# SCH_NodeMCU_PCB.net
KiCad netlist of a schematic drawn in EasyEDA
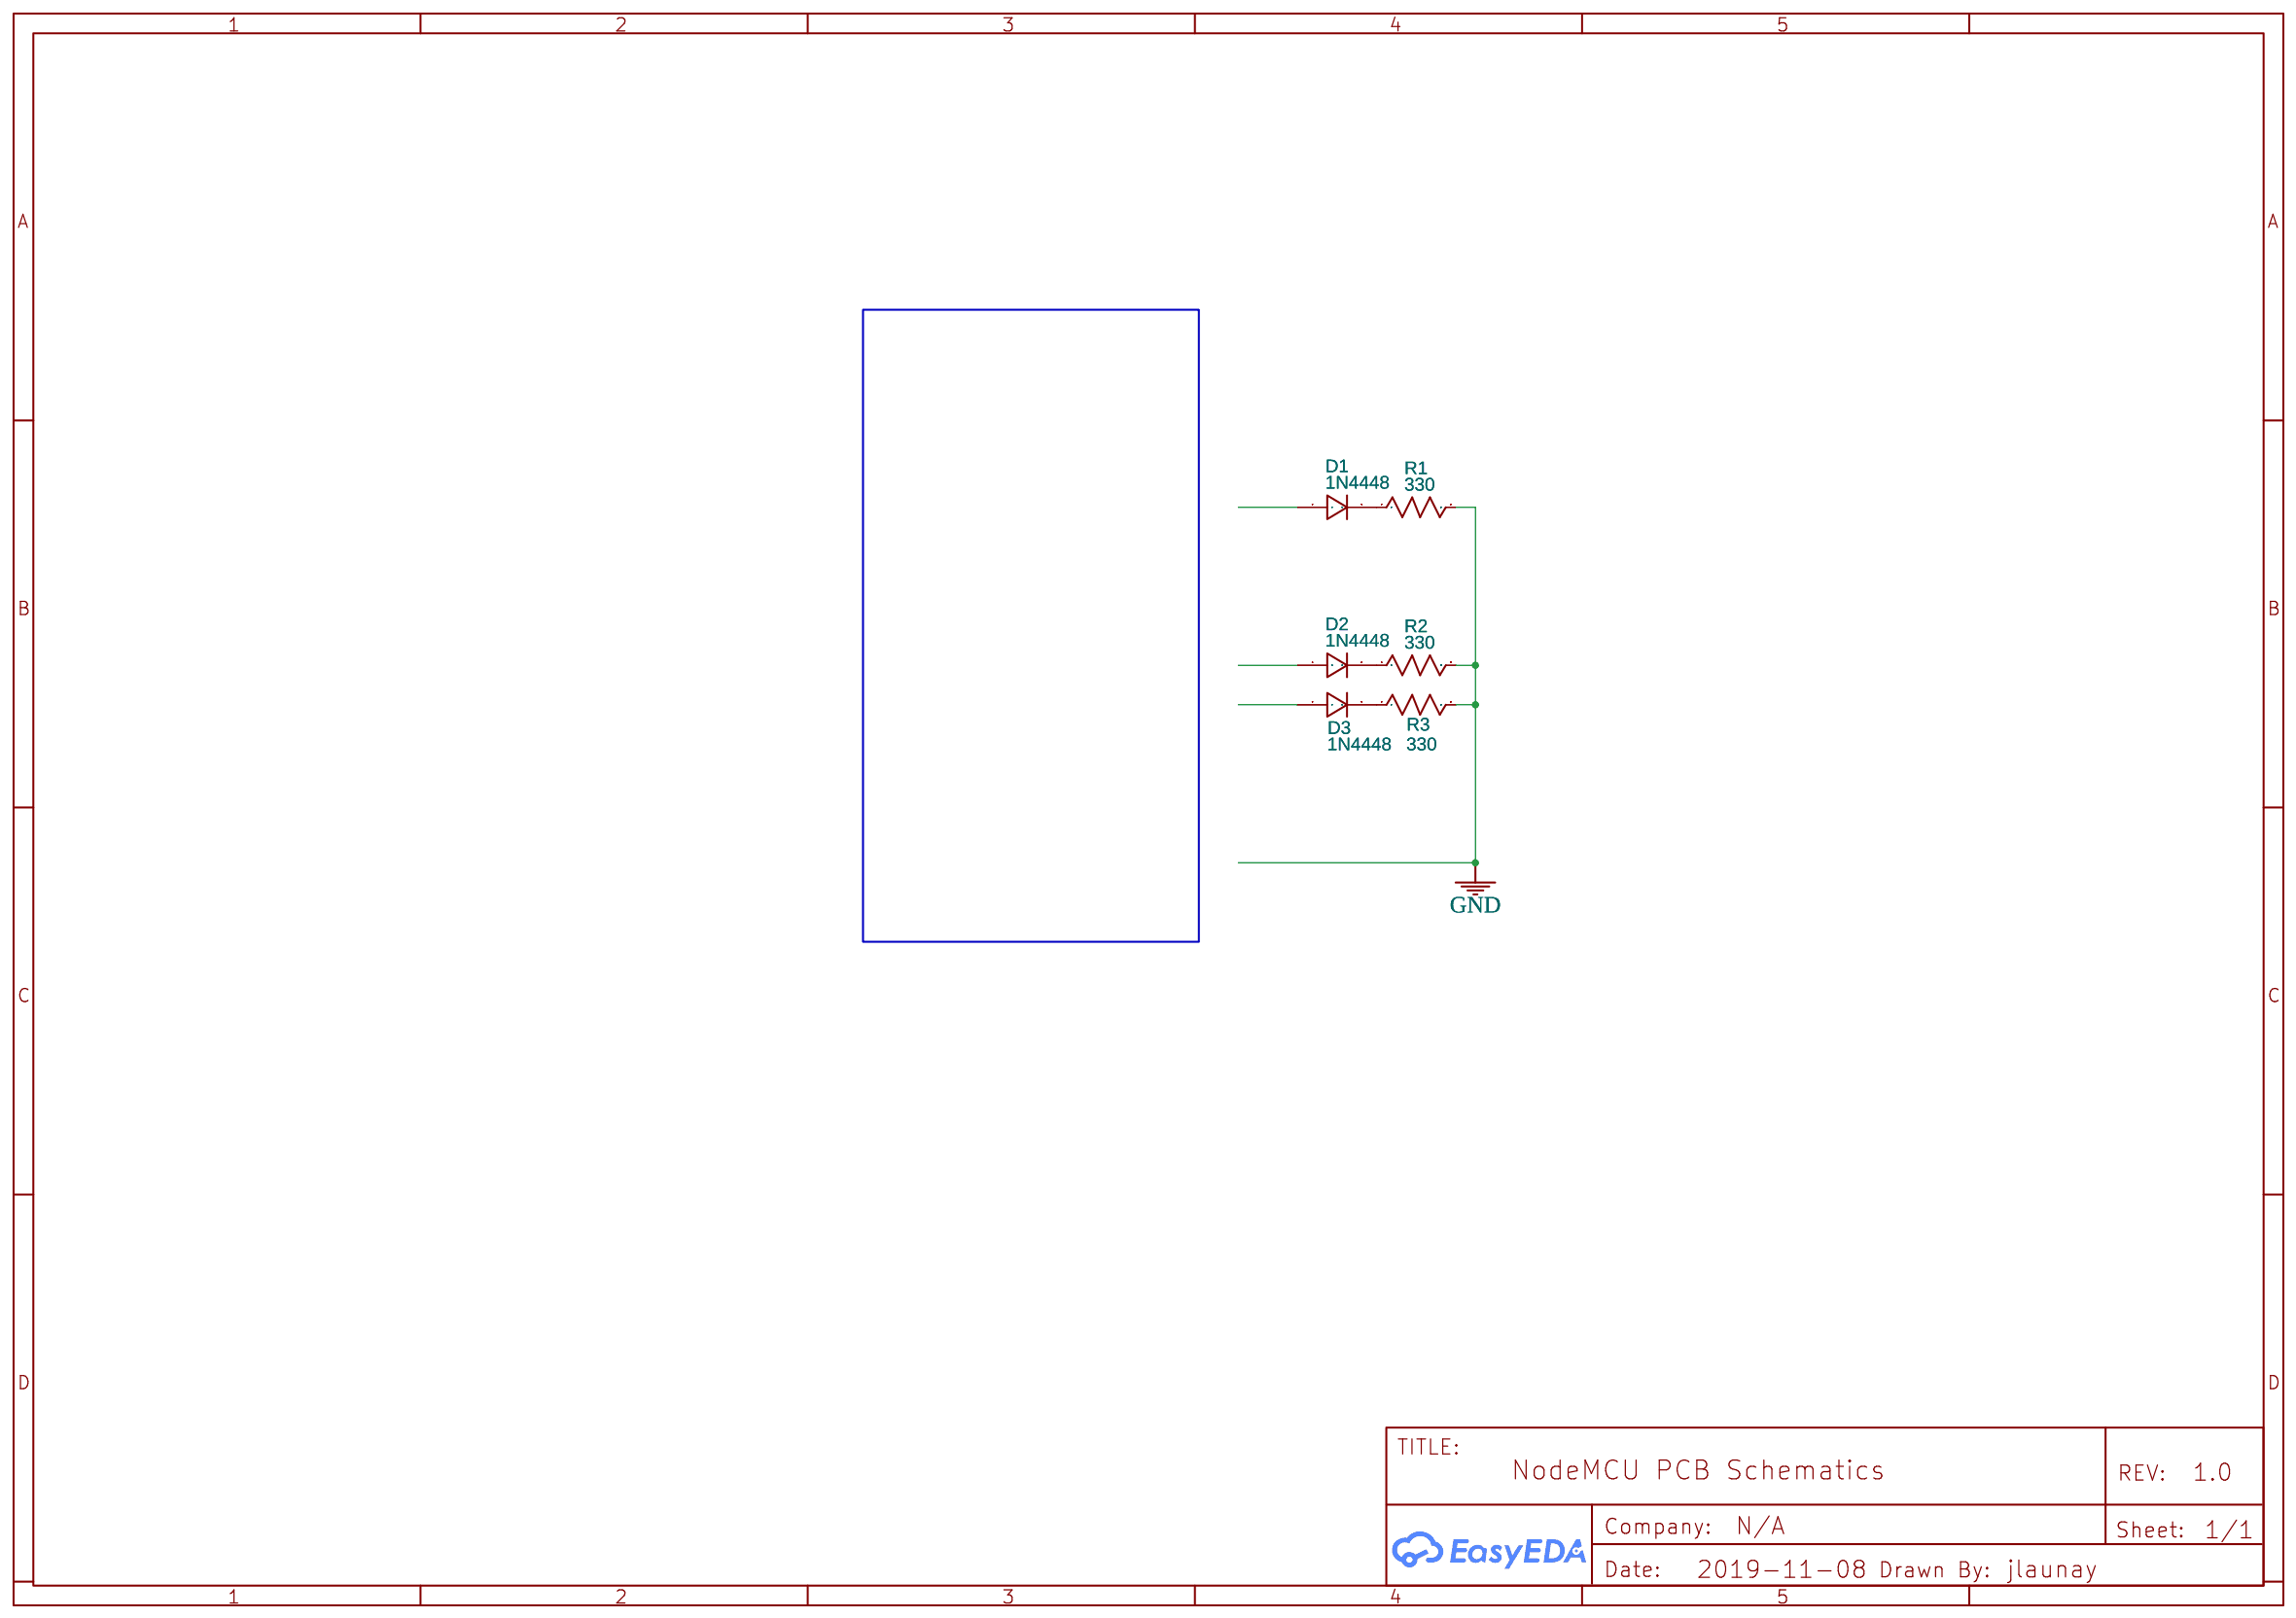
[diagram p0: schematic sheet]

(export (version "E")
  (design (tool "Eeschema 10.0.6"))
  (components
    (comp (ref "D1")
      (value "1N4448")
      (fields (field (name "BOM_Supplier Part") "C54037"))
      (libsource (lib "") (part "Unknown_670_250"))
    )
    (comp (ref "D2")
      (value "1N4448")
      (fields (field (name "BOM_Supplier Part") "C54037"))
      (libsource (lib "") (part "Unknown_670_330"))
    )
    (comp (ref "D3")
      (value "1N4448")
      (fields (field (name "BOM_Supplier Part") "C54037"))
      (libsource (lib "") (part "Unknown_670_350"))
    )
    (comp (ref "R1") (value "330") (libsource (lib "") (part "Res_AXIAL-0.3(1/8W)_US")))
    (comp (ref "R2") (value "330") (libsource (lib "") (part "Res_AXIAL-0.3(1/8W)_US")))
    (comp (ref "R3") (value "330") (libsource (lib "") (part "Res_AXIAL-0.3(1/8W)_US")))
  )
  (nets
    (net (code "1") (name "GND") (class "Default")
      (node (ref "R1") (pin "2") (pinfunction "2_2") (pintype "unspecified"))
      (node (ref "R2") (pin "2") (pinfunction "2_2") (pintype "unspecified"))
      (node (ref "R3") (pin "2") (pinfunction "2_2") (pintype "unspecified"))
    )
    (net (code "2") (name "Net-(D1-K)") (class "Default")
      (node (ref "D1") (pin "2") (pinfunction "K_2") (pintype "unspecified"))
      (node (ref "R1") (pin "1") (pinfunction "1_1") (pintype "unspecified"))
    )
    (net (code "3") (name "Net-(D2-K)") (class "Default")
      (node (ref "D2") (pin "2") (pinfunction "K_2") (pintype "unspecified"))
      (node (ref "R2") (pin "1") (pinfunction "1_1") (pintype "unspecified"))
    )
    (net (code "4") (name "Net-(D3-K)") (class "Default")
      (node (ref "D3") (pin "2") (pinfunction "K_2") (pintype "unspecified"))
      (node (ref "R3") (pin "1") (pinfunction "1_1") (pintype "unspecified"))
    )
    (net (code "5") (name "unconnected-(D1-A-Pad1)") (class "Default")
      (node (ref "D1") (pin "1") (pinfunction "A_1") (pintype "unspecified"))
    )
    (net (code "6") (name "unconnected-(D2-A-Pad1)") (class "Default")
      (node (ref "D2") (pin "1") (pinfunction "A_1") (pintype "unspecified"))
    )
    (net (code "7") (name "unconnected-(D3-A-Pad1)") (class "Default")
      (node (ref "D3") (pin "1") (pinfunction "A_1") (pintype "unspecified"))
    )
  )
)
